# Mic_to_Pi_Entire_design_including_pinout.net
KiCad netlist of a schematic drawn in EAGLE
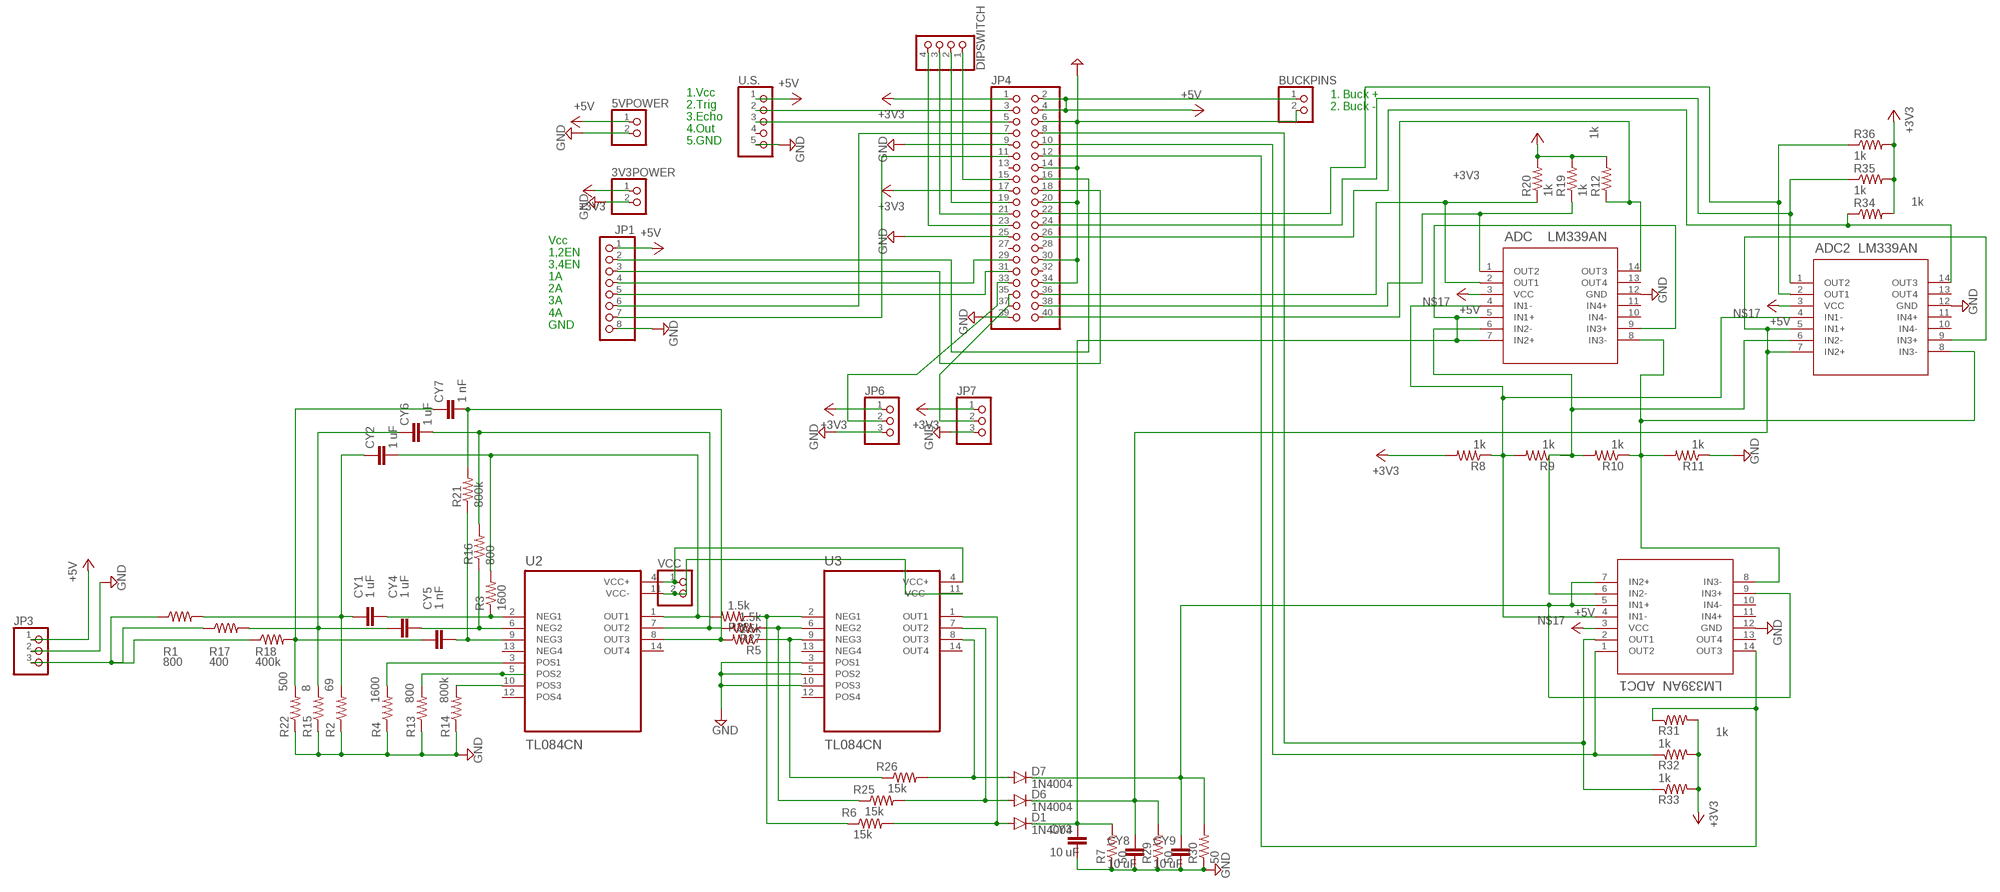
[diagram p0: schematic, sheet 1]

(export (version "E")
  (design (tool "Eeschema 10.0.6"))
  (components
    (comp (ref "3V3POWER")
      (value "PINHD-1X2")
      (footprint "eagle-import:1X02")
      (libsource (lib "eagle-import") (part "PINHD-1X2"))
    )
    (comp (ref "5VPOWER")
      (value "PINHD-1X2")
      (footprint "eagle-import:1X02")
      (libsource (lib "eagle-import") (part "PINHD-1X2"))
    )
    (comp (ref "ADC")
      (value "LM339AN")
      (footprint "eagle-import:PDIP14_646-06_ONS")
      (fields (field (name "COPYRIGHT") "Copyright (C) 2022 Ultra Librarian. All rights reserved."))
      (libsource (lib "eagle-import") (part "LM339AN"))
    )
    (comp (ref "ADC1")
      (value "LM339AN")
      (footprint "eagle-import:PDIP14_646-06_ONS")
      (fields (field (name "COPYRIGHT") "Copyright (C) 2022 Ultra Librarian. All rights reserved."))
      (libsource (lib "eagle-import") (part "LM339AN"))
    )
    (comp (ref "ADC2")
      (value "LM339AN")
      (footprint "eagle-import:PDIP14_646-06_ONS")
      (fields (field (name "COPYRIGHT") "Copyright (C) 2022 Ultra Librarian. All rights reserved."))
      (libsource (lib "eagle-import") (part "LM339AN"))
    )
    (comp (ref "BUCKPINS")
      (value "PINHD-1X2")
      (footprint "eagle-import:1X02")
      (libsource (lib "eagle-import") (part "PINHD-1X2"))
    )
    (comp (ref "CY1")
      (value "1 uF")
      (footprint "eagle-import:YC7B5")
      (libsource (lib "eagle-import") (part "CYYC7B5"))
    )
    (comp (ref "CY2")
      (value "1 uF")
      (footprint "eagle-import:YC7B5")
      (libsource (lib "eagle-import") (part "CYYC7B5"))
    )
    (comp (ref "CY3")
      (value "10 uF")
      (footprint "eagle-import:YC7B5")
      (libsource (lib "eagle-import") (part "CYYC7B5"))
    )
    (comp (ref "CY4")
      (value "1 uF")
      (footprint "eagle-import:YC7B5")
      (libsource (lib "eagle-import") (part "CYYC7B5"))
    )
    (comp (ref "CY5")
      (value "1 nF")
      (footprint "eagle-import:YC7B5")
      (libsource (lib "eagle-import") (part "CYYC7B5"))
    )
    (comp (ref "CY6")
      (value "1 uF")
      (footprint "eagle-import:YC7B5")
      (libsource (lib "eagle-import") (part "CYYC7B5"))
    )
    (comp (ref "CY7")
      (value "1 nF")
      (footprint "eagle-import:YC7B5")
      (libsource (lib "eagle-import") (part "CYYC7B5"))
    )
    (comp (ref "CY8")
      (value "10 uF")
      (footprint "eagle-import:YC7B5")
      (libsource (lib "eagle-import") (part "CYYC7B5"))
    )
    (comp (ref "CY9")
      (value "10 uF")
      (footprint "eagle-import:YC7B5")
      (libsource (lib "eagle-import") (part "CYYC7B5"))
    )
    (comp (ref "D1")
      (value "1N4004")
      (footprint "eagle-import:DO41-10")
      (libsource (lib "eagle-import") (part "1N4004"))
    )
    (comp (ref "D6")
      (value "1N4004")
      (footprint "eagle-import:DO41-10")
      (libsource (lib "eagle-import") (part "1N4004"))
    )
    (comp (ref "D7")
      (value "1N4004")
      (footprint "eagle-import:DO41-10")
      (libsource (lib "eagle-import") (part "1N4004"))
    )
    (comp (ref "DIPSWITCH")
      (value "PINHD-1X4")
      (footprint "eagle-import:1X04")
      (libsource (lib "eagle-import") (part "PINHD-1X4"))
    )
    (comp (ref "JP1")
      (value "PINHD-1X8")
      (footprint "eagle-import:1X08")
      (libsource (lib "eagle-import") (part "PINHD-1X8"))
    )
    (comp (ref "JP3")
      (value "PINHD-1X3")
      (footprint "eagle-import:1X03")
      (libsource (lib "eagle-import") (part "PINHD-1X3"))
    )
    (comp (ref "JP4")
      (value "PINHD-2X20")
      (footprint "eagle-import:2X20")
      (libsource (lib "eagle-import") (part "PINHD-2X20"))
    )
    (comp (ref "JP6")
      (value "PINHD-1X3")
      (footprint "eagle-import:1X03")
      (libsource (lib "eagle-import") (part "PINHD-1X3"))
    )
    (comp (ref "JP7")
      (value "PINHD-1X3")
      (footprint "eagle-import:1X03")
      (libsource (lib "eagle-import") (part "PINHD-1X3"))
    )
    (comp (ref "R1")
      (value "800")
      (footprint "eagle-import:0204_7")
      (libsource (lib "eagle-import") (part "R-US_0204/7"))
    )
    (comp (ref "R2")
      (value "69")
      (footprint "eagle-import:0204_7")
      (libsource (lib "eagle-import") (part "R-US_0204/7"))
    )
    (comp (ref "R3")
      (value "1600")
      (footprint "eagle-import:0204_7")
      (libsource (lib "eagle-import") (part "R-US_0204/7"))
    )
    (comp (ref "R4")
      (value "1600")
      (footprint "eagle-import:0204_7")
      (libsource (lib "eagle-import") (part "R-US_0204/7"))
    )
    (comp (ref "R5")
      (value "1.5k")
      (footprint "eagle-import:0204_7")
      (libsource (lib "eagle-import") (part "R-US_0204/7"))
    )
    (comp (ref "R6")
      (value "15k")
      (footprint "eagle-import:0204_7")
      (libsource (lib "eagle-import") (part "R-US_0204/7"))
    )
    (comp (ref "R7")
      (value "50")
      (footprint "eagle-import:0204_7")
      (libsource (lib "eagle-import") (part "R-US_0204/7"))
    )
    (comp (ref "R8")
      (value "1k")
      (footprint "eagle-import:0204_7")
      (libsource (lib "eagle-import") (part "R-US_0204/7"))
    )
    (comp (ref "R9")
      (value "1k")
      (footprint "eagle-import:0207_2V")
      (libsource (lib "eagle-import") (part "R-US_0207/2V"))
    )
    (comp (ref "R10")
      (value "1k")
      (footprint "eagle-import:0207_2V")
      (libsource (lib "eagle-import") (part "R-US_0207/2V"))
    )
    (comp (ref "R11")
      (value "1k")
      (footprint "eagle-import:0207_2V")
      (libsource (lib "eagle-import") (part "R-US_0207/2V"))
    )
    (comp (ref "R12")
      (value "1k")
      (footprint "eagle-import:0207_2V")
      (libsource (lib "eagle-import") (part "R-US_0207/2V"))
    )
    (comp (ref "R13")
      (value "800")
      (footprint "eagle-import:0204_7")
      (libsource (lib "eagle-import") (part "R-US_0204/7"))
    )
    (comp (ref "R14")
      (value "800k")
      (footprint "eagle-import:0204_7")
      (libsource (lib "eagle-import") (part "R-US_0204/7"))
    )
    (comp (ref "R15")
      (value "8")
      (footprint "eagle-import:0204_7")
      (libsource (lib "eagle-import") (part "R-US_0204/7"))
    )
    (comp (ref "R16")
      (value "800")
      (footprint "eagle-import:0204_7")
      (libsource (lib "eagle-import") (part "R-US_0204/7"))
    )
    (comp (ref "R17")
      (value "400")
      (footprint "eagle-import:0204_7")
      (libsource (lib "eagle-import") (part "R-US_0204/7"))
    )
    (comp (ref "R18")
      (value "400k")
      (footprint "eagle-import:0204_7")
      (libsource (lib "eagle-import") (part "R-US_0204/7"))
    )
    (comp (ref "R19")
      (value "1k")
      (footprint "eagle-import:0204_7")
      (libsource (lib "eagle-import") (part "R-US_0204/7"))
    )
    (comp (ref "R20")
      (value "1k")
      (footprint "eagle-import:0204_7")
      (libsource (lib "eagle-import") (part "R-US_0204/7"))
    )
    (comp (ref "R21")
      (value "800k")
      (footprint "eagle-import:0204_7")
      (libsource (lib "eagle-import") (part "R-US_0204/7"))
    )
    (comp (ref "R22")
      (value "500")
      (footprint "eagle-import:0204_7")
      (libsource (lib "eagle-import") (part "R-US_0204/7"))
    )
    (comp (ref "R25")
      (value "15k")
      (footprint "eagle-import:0204_7")
      (libsource (lib "eagle-import") (part "R-US_0204/7"))
    )
    (comp (ref "R26")
      (value "15k")
      (footprint "eagle-import:0204_7")
      (libsource (lib "eagle-import") (part "R-US_0204/7"))
    )
    (comp (ref "R27")
      (value "1.5k")
      (footprint "eagle-import:0204_7")
      (libsource (lib "eagle-import") (part "R-US_0204/7"))
    )
    (comp (ref "R28")
      (value "1.5k")
      (footprint "eagle-import:0204_7")
      (libsource (lib "eagle-import") (part "R-US_0204/7"))
    )
    (comp (ref "R29")
      (value "50")
      (footprint "eagle-import:0204_7")
      (libsource (lib "eagle-import") (part "R-US_0204/7"))
    )
    (comp (ref "R30")
      (value "50")
      (footprint "eagle-import:0204_7")
      (libsource (lib "eagle-import") (part "R-US_0204/7"))
    )
    (comp (ref "R31")
      (value "1k")
      (footprint "eagle-import:0207_2V")
      (libsource (lib "eagle-import") (part "R-US_0207/2V"))
    )
    (comp (ref "R32")
      (value "1k")
      (footprint "eagle-import:0204_7")
      (libsource (lib "eagle-import") (part "R-US_0204/7"))
    )
    (comp (ref "R33")
      (value "1k")
      (footprint "eagle-import:0204_7")
      (libsource (lib "eagle-import") (part "R-US_0204/7"))
    )
    (comp (ref "R34")
      (value "1k")
      (footprint "eagle-import:0207_2V")
      (libsource (lib "eagle-import") (part "R-US_0207/2V"))
    )
    (comp (ref "R35")
      (value "1k")
      (footprint "eagle-import:0204_7")
      (libsource (lib "eagle-import") (part "R-US_0204/7"))
    )
    (comp (ref "R36")
      (value "1k")
      (footprint "eagle-import:0204_7")
      (libsource (lib "eagle-import") (part "R-US_0204/7"))
    )
    (comp (ref "U.S.")
      (value "PINHD-1X55X2MM")
      (footprint "eagle-import:1_05X2MM")
      (libsource (lib "eagle-import") (part "PINHD-1X55X2MM"))
    )
    (comp (ref "U2")
      (value "TL084CN")
      (footprint "eagle-import:DIP794W45P254L1969H508Q14")
      (fields (field (name "DIGI-KEY_PART_NUMBER") "296-1784-5-ND") (field (name "MF") "Texas Instruments"))
      (libsource (lib "eagle-import") (part "TL084CN"))
    )
    (comp (ref "U3")
      (value "TL084CN")
      (footprint "eagle-import:DIP794W45P254L1969H508Q14")
      (fields (field (name "DIGI-KEY_PART_NUMBER") "296-1784-5-ND") (field (name "MF") "Texas Instruments"))
      (libsource (lib "eagle-import") (part "TL084CN"))
    )
    (comp (ref "VCC")
      (value "PINHD-1X2")
      (footprint "eagle-import:1X02")
      (libsource (lib "eagle-import") (part "PINHD-1X2"))
    )
  )
  (nets
    (net (code "1") (name "+3V3") (class "Default")
      (node (ref "3V3POWER") (pin "1") (pinfunction "1_1") (pintype "passive"))
      (node (ref "JP4") (pin "1") (pinfunction "1_1") (pintype "passive"))
      (node (ref "JP4") (pin "17") (pinfunction "17_17") (pintype "passive"))
      (node (ref "JP6") (pin "1") (pinfunction "1_1") (pintype "passive"))
      (node (ref "JP7") (pin "1") (pinfunction "1_1") (pintype "passive"))
      (node (ref "R12") (pin "2") (pinfunction "2_2") (pintype "passive"))
      (node (ref "R19") (pin "2") (pinfunction "2_2") (pintype "passive"))
      (node (ref "R20") (pin "2") (pinfunction "2_2") (pintype "passive"))
      (node (ref "R31") (pin "2") (pinfunction "2_2") (pintype "passive"))
      (node (ref "R32") (pin "2") (pinfunction "2_2") (pintype "passive"))
      (node (ref "R33") (pin "2") (pinfunction "2_2") (pintype "passive"))
      (node (ref "R34") (pin "2") (pinfunction "2_2") (pintype "passive"))
      (node (ref "R35") (pin "2") (pinfunction "2_2") (pintype "passive"))
      (node (ref "R36") (pin "2") (pinfunction "2_2") (pintype "passive"))
      (node (ref "R8") (pin "2") (pinfunction "2_2") (pintype "passive"))
    )
    (net (code "2") (name "+5V") (class "Default")
      (node (ref "5VPOWER") (pin "1") (pinfunction "1_1") (pintype "passive"))
      (node (ref "ADC") (pin "3") (pinfunction "VCC_3") (pintype "power_in"))
      (node (ref "ADC1") (pin "3") (pinfunction "VCC_3") (pintype "power_in"))
      (node (ref "ADC2") (pin "3") (pinfunction "VCC_3") (pintype "power_in"))
      (node (ref "BUCKPINS") (pin "1") (pinfunction "1_1") (pintype "passive"))
      (node (ref "JP1") (pin "1") (pinfunction "1_1") (pintype "passive"))
      (node (ref "JP3") (pin "1") (pinfunction "1_1") (pintype "passive"))
      (node (ref "JP4") (pin "2") (pinfunction "2_2") (pintype "passive"))
      (node (ref "JP4") (pin "4") (pinfunction "4_4") (pintype "passive"))
      (node (ref "U.S.") (pin "1") (pinfunction "1_1") (pintype "passive"))
    )
    (net (code "3") (name "/N$17") (class "Default")
      (node (ref "ADC") (pin "4") (pinfunction "IN1-_4") (pintype "input"))
      (node (ref "ADC1") (pin "4") (pinfunction "IN1-_4") (pintype "input"))
      (node (ref "ADC2") (pin "4") (pinfunction "IN1-_4") (pintype "input"))
      (node (ref "R8") (pin "1") (pinfunction "1_1") (pintype "passive"))
      (node (ref "R9") (pin "2") (pinfunction "2_2") (pintype "passive"))
    )
    (net (code "4") (name "GND") (class "Default")
      (node (ref "3V3POWER") (pin "2") (pinfunction "2_2") (pintype "passive"))
      (node (ref "5VPOWER") (pin "2") (pinfunction "2_2") (pintype "passive"))
      (node (ref "ADC") (pin "12") (pinfunction "GND_12") (pintype "passive"))
      (node (ref "ADC1") (pin "12") (pinfunction "GND_12") (pintype "passive"))
      (node (ref "ADC2") (pin "12") (pinfunction "GND_12") (pintype "passive"))
      (node (ref "BUCKPINS") (pin "2") (pinfunction "2_2") (pintype "passive"))
      (node (ref "CY3") (pin "2") (pinfunction "2_2") (pintype "passive"))
      (node (ref "CY8") (pin "2") (pinfunction "2_2") (pintype "passive"))
      (node (ref "CY9") (pin "2") (pinfunction "2_2") (pintype "passive"))
      (node (ref "JP1") (pin "8") (pinfunction "8_8") (pintype "passive"))
      (node (ref "JP3") (pin "2") (pinfunction "2_2") (pintype "passive"))
      (node (ref "JP4") (pin "14") (pinfunction "14_14") (pintype "passive"))
      (node (ref "JP4") (pin "20") (pinfunction "20_20") (pintype "passive"))
      (node (ref "JP4") (pin "25") (pinfunction "25_25") (pintype "passive"))
      (node (ref "JP4") (pin "30") (pinfunction "30_30") (pintype "passive"))
      (node (ref "JP4") (pin "34") (pinfunction "34_34") (pintype "passive"))
      (node (ref "JP4") (pin "39") (pinfunction "39_39") (pintype "passive"))
      (node (ref "JP4") (pin "6") (pinfunction "6_6") (pintype "passive"))
      (node (ref "JP4") (pin "9") (pinfunction "9_9") (pintype "passive"))
      (node (ref "JP6") (pin "3") (pinfunction "3_3") (pintype "passive"))
      (node (ref "JP7") (pin "3") (pinfunction "3_3") (pintype "passive"))
      (node (ref "R11") (pin "1") (pinfunction "1_1") (pintype "passive"))
      (node (ref "R13") (pin "1") (pinfunction "1_1") (pintype "passive"))
      (node (ref "R14") (pin "1") (pinfunction "1_1") (pintype "passive"))
      (node (ref "R15") (pin "1") (pinfunction "1_1") (pintype "passive"))
      (node (ref "R2") (pin "1") (pinfunction "1_1") (pintype "passive"))
      (node (ref "R22") (pin "1") (pinfunction "1_1") (pintype "passive"))
      (node (ref "R29") (pin "1") (pinfunction "1_1") (pintype "passive"))
      (node (ref "R30") (pin "1") (pinfunction "1_1") (pintype "passive"))
      (node (ref "R4") (pin "1") (pinfunction "1_1") (pintype "passive"))
      (node (ref "R7") (pin "1") (pinfunction "1_1") (pintype "passive"))
      (node (ref "U.S.") (pin "5") (pinfunction "5_5") (pintype "passive"))
      (node (ref "U3") (pin "10") (pinfunction "POS3_10") (pintype "input"))
      (node (ref "U3") (pin "3") (pinfunction "POS1_3") (pintype "input"))
      (node (ref "U3") (pin "5") (pinfunction "POS2_5") (pintype "input"))
    )
    (net (code "5") (name "Net-(ADC-IN1+)") (class "Default")
      (node (ref "ADC") (pin "5") (pinfunction "IN1+_5") (pintype "input"))
      (node (ref "ADC") (pin "7") (pinfunction "IN2+_7") (pintype "input"))
      (node (ref "ADC") (pin "9") (pinfunction "IN3+_9") (pintype "input"))
      (node (ref "CY3") (pin "1") (pinfunction "1_1") (pintype "passive"))
      (node (ref "D1") (pin "C") (pinfunction "C_C") (pintype "passive"))
      (node (ref "R7") (pin "2") (pinfunction "2_2") (pintype "passive"))
    )
    (net (code "6") (name "Net-(ADC-IN2-)") (class "Default")
      (node (ref "ADC") (pin "6") (pinfunction "IN2-_6") (pintype "input"))
      (node (ref "ADC1") (pin "6") (pinfunction "IN2-_6") (pintype "input"))
      (node (ref "ADC2") (pin "6") (pinfunction "IN2-_6") (pintype "input"))
      (node (ref "R10") (pin "2") (pinfunction "2_2") (pintype "passive"))
      (node (ref "R9") (pin "1") (pinfunction "1_1") (pintype "passive"))
    )
    (net (code "7") (name "Net-(ADC-IN3-)") (class "Default")
      (node (ref "ADC") (pin "8") (pinfunction "IN3-_8") (pintype "input"))
      (node (ref "ADC1") (pin "8") (pinfunction "IN3-_8") (pintype "input"))
      (node (ref "ADC2") (pin "8") (pinfunction "IN3-_8") (pintype "input"))
      (node (ref "R10") (pin "1") (pinfunction "1_1") (pintype "passive"))
      (node (ref "R11") (pin "2") (pinfunction "2_2") (pintype "passive"))
    )
    (net (code "8") (name "Net-(ADC-OUT1)") (class "Default")
      (node (ref "ADC") (pin "2") (pinfunction "OUT1_2") (pintype "output"))
      (node (ref "JP4") (pin "36") (pinfunction "36_36") (pintype "passive"))
      (node (ref "R20") (pin "1") (pinfunction "1_1") (pintype "passive"))
    )
    (net (code "9") (name "Net-(ADC-OUT2)") (class "Default")
      (node (ref "ADC") (pin "1") (pinfunction "OUT2_1") (pintype "output"))
      (node (ref "JP4") (pin "38") (pinfunction "38_38") (pintype "passive"))
      (node (ref "R19") (pin "1") (pinfunction "1_1") (pintype "passive"))
    )
    (net (code "10") (name "Net-(ADC-OUT3)") (class "Default")
      (node (ref "ADC") (pin "14") (pinfunction "OUT3_14") (pintype "output"))
      (node (ref "JP4") (pin "40") (pinfunction "40_40") (pintype "passive"))
      (node (ref "R12") (pin "1") (pinfunction "1_1") (pintype "passive"))
    )
    (net (code "11") (name "Net-(ADC1-IN1+)") (class "Default")
      (node (ref "ADC1") (pin "5") (pinfunction "IN1+_5") (pintype "input"))
      (node (ref "ADC1") (pin "7") (pinfunction "IN2+_7") (pintype "input"))
      (node (ref "ADC1") (pin "9") (pinfunction "IN3+_9") (pintype "input"))
      (node (ref "CY9") (pin "1") (pinfunction "1_1") (pintype "passive"))
      (node (ref "D7") (pin "C") (pinfunction "C_C") (pintype "passive"))
      (node (ref "R30") (pin "2") (pinfunction "2_2") (pintype "passive"))
    )
    (net (code "12") (name "Net-(ADC1-OUT1)") (class "Default")
      (node (ref "ADC1") (pin "2") (pinfunction "OUT1_2") (pintype "output"))
      (node (ref "JP4") (pin "8") (pinfunction "8_8") (pintype "passive"))
      (node (ref "R33") (pin "1") (pinfunction "1_1") (pintype "passive"))
    )
    (net (code "13") (name "Net-(ADC1-OUT2)") (class "Default")
      (node (ref "ADC1") (pin "1") (pinfunction "OUT2_1") (pintype "output"))
      (node (ref "JP4") (pin "10") (pinfunction "10_10") (pintype "passive"))
      (node (ref "R32") (pin "1") (pinfunction "1_1") (pintype "passive"))
    )
    (net (code "14") (name "Net-(ADC1-OUT3)") (class "Default")
      (node (ref "ADC1") (pin "14") (pinfunction "OUT3_14") (pintype "output"))
      (node (ref "JP4") (pin "12") (pinfunction "12_12") (pintype "passive"))
      (node (ref "R31") (pin "1") (pinfunction "1_1") (pintype "passive"))
    )
    (net (code "15") (name "Net-(ADC2-IN1+)") (class "Default")
      (node (ref "ADC2") (pin "5") (pinfunction "IN1+_5") (pintype "input"))
      (node (ref "ADC2") (pin "7") (pinfunction "IN2+_7") (pintype "input"))
      (node (ref "ADC2") (pin "9") (pinfunction "IN3+_9") (pintype "input"))
      (node (ref "CY8") (pin "1") (pinfunction "1_1") (pintype "passive"))
      (node (ref "D6") (pin "C") (pinfunction "C_C") (pintype "passive"))
      (node (ref "R29") (pin "2") (pinfunction "2_2") (pintype "passive"))
    )
    (net (code "16") (name "Net-(ADC2-OUT1)") (class "Default")
      (node (ref "ADC2") (pin "2") (pinfunction "OUT1_2") (pintype "output"))
      (node (ref "JP4") (pin "22") (pinfunction "22_22") (pintype "passive"))
      (node (ref "R36") (pin "1") (pinfunction "1_1") (pintype "passive"))
    )
    (net (code "17") (name "Net-(ADC2-OUT2)") (class "Default")
      (node (ref "ADC2") (pin "1") (pinfunction "OUT2_1") (pintype "output"))
      (node (ref "JP4") (pin "24") (pinfunction "24_24") (pintype "passive"))
      (node (ref "R35") (pin "1") (pinfunction "1_1") (pintype "passive"))
    )
    (net (code "18") (name "Net-(ADC2-OUT3)") (class "Default")
      (node (ref "ADC2") (pin "14") (pinfunction "OUT3_14") (pintype "output"))
      (node (ref "JP4") (pin "26") (pinfunction "26_26") (pintype "passive"))
      (node (ref "R34") (pin "1") (pinfunction "1_1") (pintype "passive"))
    )
    (net (code "19") (name "Net-(CY1-Pad1)") (class "Default")
      (node (ref "CY1") (pin "1") (pinfunction "1_1") (pintype "passive"))
      (node (ref "CY2") (pin "1") (pinfunction "1_1") (pintype "passive"))
      (node (ref "R1") (pin "2") (pinfunction "2_2") (pintype "passive"))
      (node (ref "R2") (pin "2") (pinfunction "2_2") (pintype "passive"))
    )
    (net (code "20") (name "Net-(CY4-Pad1)") (class "Default")
      (node (ref "CY4") (pin "1") (pinfunction "1_1") (pintype "passive"))
      (node (ref "CY6") (pin "1") (pinfunction "1_1") (pintype "passive"))
      (node (ref "R15") (pin "2") (pinfunction "2_2") (pintype "passive"))
      (node (ref "R17") (pin "2") (pinfunction "2_2") (pintype "passive"))
    )
    (net (code "21") (name "Net-(CY5-Pad1)") (class "Default")
      (node (ref "CY5") (pin "1") (pinfunction "1_1") (pintype "passive"))
      (node (ref "CY7") (pin "1") (pinfunction "1_1") (pintype "passive"))
      (node (ref "R18") (pin "2") (pinfunction "2_2") (pintype "passive"))
      (node (ref "R22") (pin "2") (pinfunction "2_2") (pintype "passive"))
    )
    (net (code "22") (name "Net-(DIPSWITCH-Pad1)") (class "Default")
      (node (ref "DIPSWITCH") (pin "1") (pinfunction "1_1") (pintype "passive"))
      (node (ref "JP4") (pin "15") (pinfunction "15_15") (pintype "passive"))
    )
    (net (code "23") (name "Net-(DIPSWITCH-Pad2)") (class "Default")
      (node (ref "DIPSWITCH") (pin "2") (pinfunction "2_2") (pintype "passive"))
      (node (ref "JP4") (pin "19") (pinfunction "19_19") (pintype "passive"))
    )
    (net (code "24") (name "Net-(DIPSWITCH-Pad3)") (class "Default")
      (node (ref "DIPSWITCH") (pin "3") (pinfunction "3_3") (pintype "passive"))
      (node (ref "JP4") (pin "21") (pinfunction "21_21") (pintype "passive"))
    )
    (net (code "25") (name "Net-(DIPSWITCH-Pad4)") (class "Default")
      (node (ref "DIPSWITCH") (pin "4") (pinfunction "4_4") (pintype "passive"))
      (node (ref "JP4") (pin "23") (pinfunction "23_23") (pintype "passive"))
    )
    (net (code "26") (name "Net-(JP1-Pad2)") (class "Default")
      (node (ref "JP1") (pin "2") (pinfunction "2_2") (pintype "passive"))
      (node (ref "JP4") (pin "16") (pinfunction "16_16") (pintype "passive"))
    )
    (net (code "27") (name "Net-(JP1-Pad3)") (class "Default")
      (node (ref "JP1") (pin "3") (pinfunction "3_3") (pintype "passive"))
      (node (ref "JP4") (pin "18") (pinfunction "18_18") (pintype "passive"))
    )
    (net (code "28") (name "Net-(JP1-Pad4)") (class "Default")
      (node (ref "JP1") (pin "4") (pinfunction "4_4") (pintype "passive"))
      (node (ref "JP4") (pin "29") (pinfunction "29_29") (pintype "passive"))
    )
    (net (code "29") (name "Net-(JP1-Pad5)") (class "Default")
      (node (ref "JP1") (pin "5") (pinfunction "5_5") (pintype "passive"))
      (node (ref "JP4") (pin "31") (pinfunction "31_31") (pintype "passive"))
    )
    (net (code "30") (name "Net-(JP1-Pad6)") (class "Default")
      (node (ref "JP1") (pin "6") (pinfunction "6_6") (pintype "passive"))
      (node (ref "JP4") (pin "7") (pinfunction "7_7") (pintype "passive"))
    )
    (net (code "31") (name "Net-(JP1-Pad7)") (class "Default")
      (node (ref "JP1") (pin "7") (pinfunction "7_7") (pintype "passive"))
      (node (ref "JP4") (pin "11") (pinfunction "11_11") (pintype "passive"))
    )
    (net (code "32") (name "Net-(JP3-Pad3)") (class "Default")
      (node (ref "JP3") (pin "3") (pinfunction "3_3") (pintype "passive"))
      (node (ref "R1") (pin "1") (pinfunction "1_1") (pintype "passive"))
      (node (ref "R17") (pin "1") (pinfunction "1_1") (pintype "passive"))
      (node (ref "R18") (pin "1") (pinfunction "1_1") (pintype "passive"))
    )
    (net (code "33") (name "Net-(JP4-Pad3)") (class "Default")
      (node (ref "JP4") (pin "3") (pinfunction "3_3") (pintype "passive"))
      (node (ref "U.S.") (pin "2") (pinfunction "2_2") (pintype "passive"))
    )
    (net (code "34") (name "Net-(JP4-Pad5)") (class "Default")
      (node (ref "JP4") (pin "5") (pinfunction "5_5") (pintype "passive"))
      (node (ref "U.S.") (pin "3") (pinfunction "3_3") (pintype "passive"))
    )
    (net (code "35") (name "Net-(JP4-Pad33)") (class "Default")
      (node (ref "JP4") (pin "33") (pinfunction "33_33") (pintype "passive"))
      (node (ref "JP6") (pin "2") (pinfunction "2_2") (pintype "passive"))
    )
    (net (code "36") (name "Net-(JP4-Pad35)") (class "Default")
      (node (ref "JP4") (pin "35") (pinfunction "35_35") (pintype "passive"))
      (node (ref "JP4") (pin "37") (pinfunction "37_37") (pintype "passive"))
      (node (ref "JP7") (pin "2") (pinfunction "2_2") (pintype "passive"))
    )
    (net (code "37") (name "Net-(U2-NEG1)") (class "Default")
      (node (ref "CY1") (pin "2") (pinfunction "2_2") (pintype "passive"))
      (node (ref "R3") (pin "1") (pinfunction "1_1") (pintype "passive"))
      (node (ref "U2") (pin "2") (pinfunction "NEG1_2") (pintype "input"))
    )
    (net (code "38") (name "Net-(U2-NEG2)") (class "Default")
      (node (ref "CY4") (pin "2") (pinfunction "2_2") (pintype "passive"))
      (node (ref "R16") (pin "1") (pinfunction "1_1") (pintype "passive"))
      (node (ref "U2") (pin "6") (pinfunction "NEG2_6") (pintype "input"))
    )
    (net (code "39") (name "Net-(U2-NEG3)") (class "Default")
      (node (ref "CY5") (pin "2") (pinfunction "2_2") (pintype "passive"))
      (node (ref "R21") (pin "1") (pinfunction "1_1") (pintype "passive"))
      (node (ref "U2") (pin "9") (pinfunction "NEG3_9") (pintype "input"))
    )
    (net (code "40") (name "Net-(U2-OUT1)") (class "Default")
      (node (ref "CY2") (pin "2") (pinfunction "2_2") (pintype "passive"))
      (node (ref "R28") (pin "2") (pinfunction "2_2") (pintype "passive"))
      (node (ref "R3") (pin "2") (pinfunction "2_2") (pintype "passive"))
      (node (ref "U2") (pin "1") (pinfunction "OUT1_1") (pintype "output"))
    )
    (net (code "41") (name "Net-(U2-OUT2)") (class "Default")
      (node (ref "CY6") (pin "2") (pinfunction "2_2") (pintype "passive"))
      (node (ref "R16") (pin "2") (pinfunction "2_2") (pintype "passive"))
      (node (ref "R27") (pin "2") (pinfunction "2_2") (pintype "passive"))
      (node (ref "U2") (pin "7") (pinfunction "OUT2_7") (pintype "output"))
    )
    (net (code "42") (name "Net-(U2-OUT3)") (class "Default")
      (node (ref "CY7") (pin "2") (pinfunction "2_2") (pintype "passive"))
      (node (ref "R21") (pin "2") (pinfunction "2_2") (pintype "passive"))
      (node (ref "R5") (pin "2") (pinfunction "2_2") (pintype "passive"))
      (node (ref "U2") (pin "8") (pinfunction "OUT3_8") (pintype "output"))
    )
    (net (code "43") (name "Net-(U2-POS1)") (class "Default")
      (node (ref "R4") (pin "2") (pinfunction "2_2") (pintype "passive"))
      (node (ref "U2") (pin "3") (pinfunction "POS1_3") (pintype "input"))
    )
    (net (code "44") (name "Net-(U2-POS2)") (class "Default")
      (node (ref "R13") (pin "2") (pinfunction "2_2") (pintype "passive"))
      (node (ref "U2") (pin "5") (pinfunction "POS2_5") (pintype "input"))
    )
    (net (code "45") (name "Net-(U2-POS3)") (class "Default")
      (node (ref "R14") (pin "2") (pinfunction "2_2") (pintype "passive"))
      (node (ref "U2") (pin "10") (pinfunction "POS3_10") (pintype "input"))
    )
    (net (code "46") (name "Net-(U2-VCC+)") (class "Default")
      (node (ref "U2") (pin "4") (pinfunction "VCC+_4") (pintype "power_in"))
      (node (ref "U3") (pin "4") (pinfunction "VCC+_4") (pintype "power_in"))
      (node (ref "VCC") (pin "1") (pinfunction "1_1") (pintype "passive"))
    )
    (net (code "47") (name "Net-(U2-VCC-)") (class "Default")
      (node (ref "U2") (pin "11") (pinfunction "VCC-_11") (pintype "power_in"))
      (node (ref "U3") (pin "11") (pinfunction "VCC-_11") (pintype "power_in"))
      (node (ref "VCC") (pin "2") (pinfunction "2_2") (pintype "passive"))
    )
    (net (code "48") (name "Net-(U3-NEG1)") (class "Default")
      (node (ref "R28") (pin "1") (pinfunction "1_1") (pintype "passive"))
      (node (ref "R6") (pin "1") (pinfunction "1_1") (pintype "passive"))
      (node (ref "U3") (pin "2") (pinfunction "NEG1_2") (pintype "input"))
    )
    (net (code "49") (name "Net-(U3-NEG2)") (class "Default")
      (node (ref "R25") (pin "1") (pinfunction "1_1") (pintype "passive"))
      (node (ref "R27") (pin "1") (pinfunction "1_1") (pintype "passive"))
      (node (ref "U3") (pin "6") (pinfunction "NEG2_6") (pintype "input"))
    )
    (net (code "50") (name "Net-(U3-NEG3)") (class "Default")
      (node (ref "R26") (pin "1") (pinfunction "1_1") (pintype "passive"))
      (node (ref "R5") (pin "1") (pinfunction "1_1") (pintype "passive"))
      (node (ref "U3") (pin "9") (pinfunction "NEG3_9") (pintype "input"))
    )
    (net (code "51") (name "Net-(U3-OUT1)") (class "Default")
      (node (ref "D1") (pin "A") (pinfunction "A_A") (pintype "passive"))
      (node (ref "R6") (pin "2") (pinfunction "2_2") (pintype "passive"))
      (node (ref "U3") (pin "1") (pinfunction "OUT1_1") (pintype "output"))
    )
    (net (code "52") (name "Net-(U3-OUT2)") (class "Default")
      (node (ref "D6") (pin "A") (pinfunction "A_A") (pintype "passive"))
      (node (ref "R25") (pin "2") (pinfunction "2_2") (pintype "passive"))
      (node (ref "U3") (pin "7") (pinfunction "OUT2_7") (pintype "output"))
    )
    (net (code "53") (name "Net-(U3-OUT3)") (class "Default")
      (node (ref "D7") (pin "A") (pinfunction "A_A") (pintype "passive"))
      (node (ref "R26") (pin "2") (pinfunction "2_2") (pintype "passive"))
      (node (ref "U3") (pin "8") (pinfunction "OUT3_8") (pintype "output"))
    )
    (net (code "54") (name "unconnected-(ADC-IN4+-Pad11)") (class "Default")
      (node (ref "ADC") (pin "11") (pinfunction "IN4+_11") (pintype "input"))
    )
    (net (code "55") (name "unconnected-(ADC-IN4--Pad10)") (class "Default")
      (node (ref "ADC") (pin "10") (pinfunction "IN4-_10") (pintype "input"))
    )
    (net (code "56") (name "unconnected-(ADC-OUT4-Pad13)") (class "Default")
      (node (ref "ADC") (pin "13") (pinfunction "OUT4_13") (pintype "output"))
    )
    (net (code "57") (name "unconnected-(ADC1-IN4+-Pad11)") (class "Default")
      (node (ref "ADC1") (pin "11") (pinfunction "IN4+_11") (pintype "input"))
    )
    (net (code "58") (name "unconnected-(ADC1-IN4--Pad10)") (class "Default")
      (node (ref "ADC1") (pin "10") (pinfunction "IN4-_10") (pintype "input"))
    )
    (net (code "59") (name "unconnected-(ADC1-OUT4-Pad13)") (class "Default")
      (node (ref "ADC1") (pin "13") (pinfunction "OUT4_13") (pintype "output"))
    )
    (net (code "60") (name "unconnected-(ADC2-IN4+-Pad11)") (class "Default")
      (node (ref "ADC2") (pin "11") (pinfunction "IN4+_11") (pintype "input"))
    )
    (net (code "61") (name "unconnected-(ADC2-IN4--Pad10)") (class "Default")
      (node (ref "ADC2") (pin "10") (pinfunction "IN4-_10") (pintype "input"))
    )
    (net (code "62") (name "unconnected-(ADC2-OUT4-Pad13)") (class "Default")
      (node (ref "ADC2") (pin "13") (pinfunction "OUT4_13") (pintype "output"))
    )
    (net (code "63") (name "unconnected-(JP4-Pad13)") (class "Default")
      (node (ref "JP4") (pin "13") (pinfunction "13_13") (pintype "passive"))
    )
    (net (code "64") (name "unconnected-(JP4-Pad27)") (class "Default")
      (node (ref "JP4") (pin "27") (pinfunction "27_27") (pintype "passive"))
    )
    (net (code "65") (name "unconnected-(JP4-Pad28)") (class "Default")
      (node (ref "JP4") (pin "28") (pinfunction "28_28") (pintype "passive"))
    )
    (net (code "66") (name "unconnected-(JP4-Pad32)") (class "Default")
      (node (ref "JP4") (pin "32") (pinfunction "32_32") (pintype "passive"))
    )
    (net (code "67") (name "unconnected-(U.S.-Pad4)") (class "Default")
      (node (ref "U.S.") (pin "4") (pinfunction "4_4") (pintype "passive"))
    )
    (net (code "68") (name "unconnected-(U2-NEG4-Pad13)") (class "Default")
      (node (ref "U2") (pin "13") (pinfunction "NEG4_13") (pintype "input"))
    )
    (net (code "69") (name "unconnected-(U2-OUT4-Pad14)") (class "Default")
      (node (ref "U2") (pin "14") (pinfunction "OUT4_14") (pintype "output"))
    )
    (net (code "70") (name "unconnected-(U2-POS4-Pad12)") (class "Default")
      (node (ref "U2") (pin "12") (pinfunction "POS4_12") (pintype "input"))
    )
    (net (code "71") (name "unconnected-(U3-NEG4-Pad13)") (class "Default")
      (node (ref "U3") (pin "13") (pinfunction "NEG4_13") (pintype "input"))
    )
    (net (code "72") (name "unconnected-(U3-OUT4-Pad14)") (class "Default")
      (node (ref "U3") (pin "14") (pinfunction "OUT4_14") (pintype "output"))
    )
    (net (code "73") (name "unconnected-(U3-POS4-Pad12)") (class "Default")
      (node (ref "U3") (pin "12") (pinfunction "POS4_12") (pintype "input"))
    )
  )
)
